# Artemis_HS_Expansion_Connector.net
KiCad netlist of a schematic drawn in Altium Designer
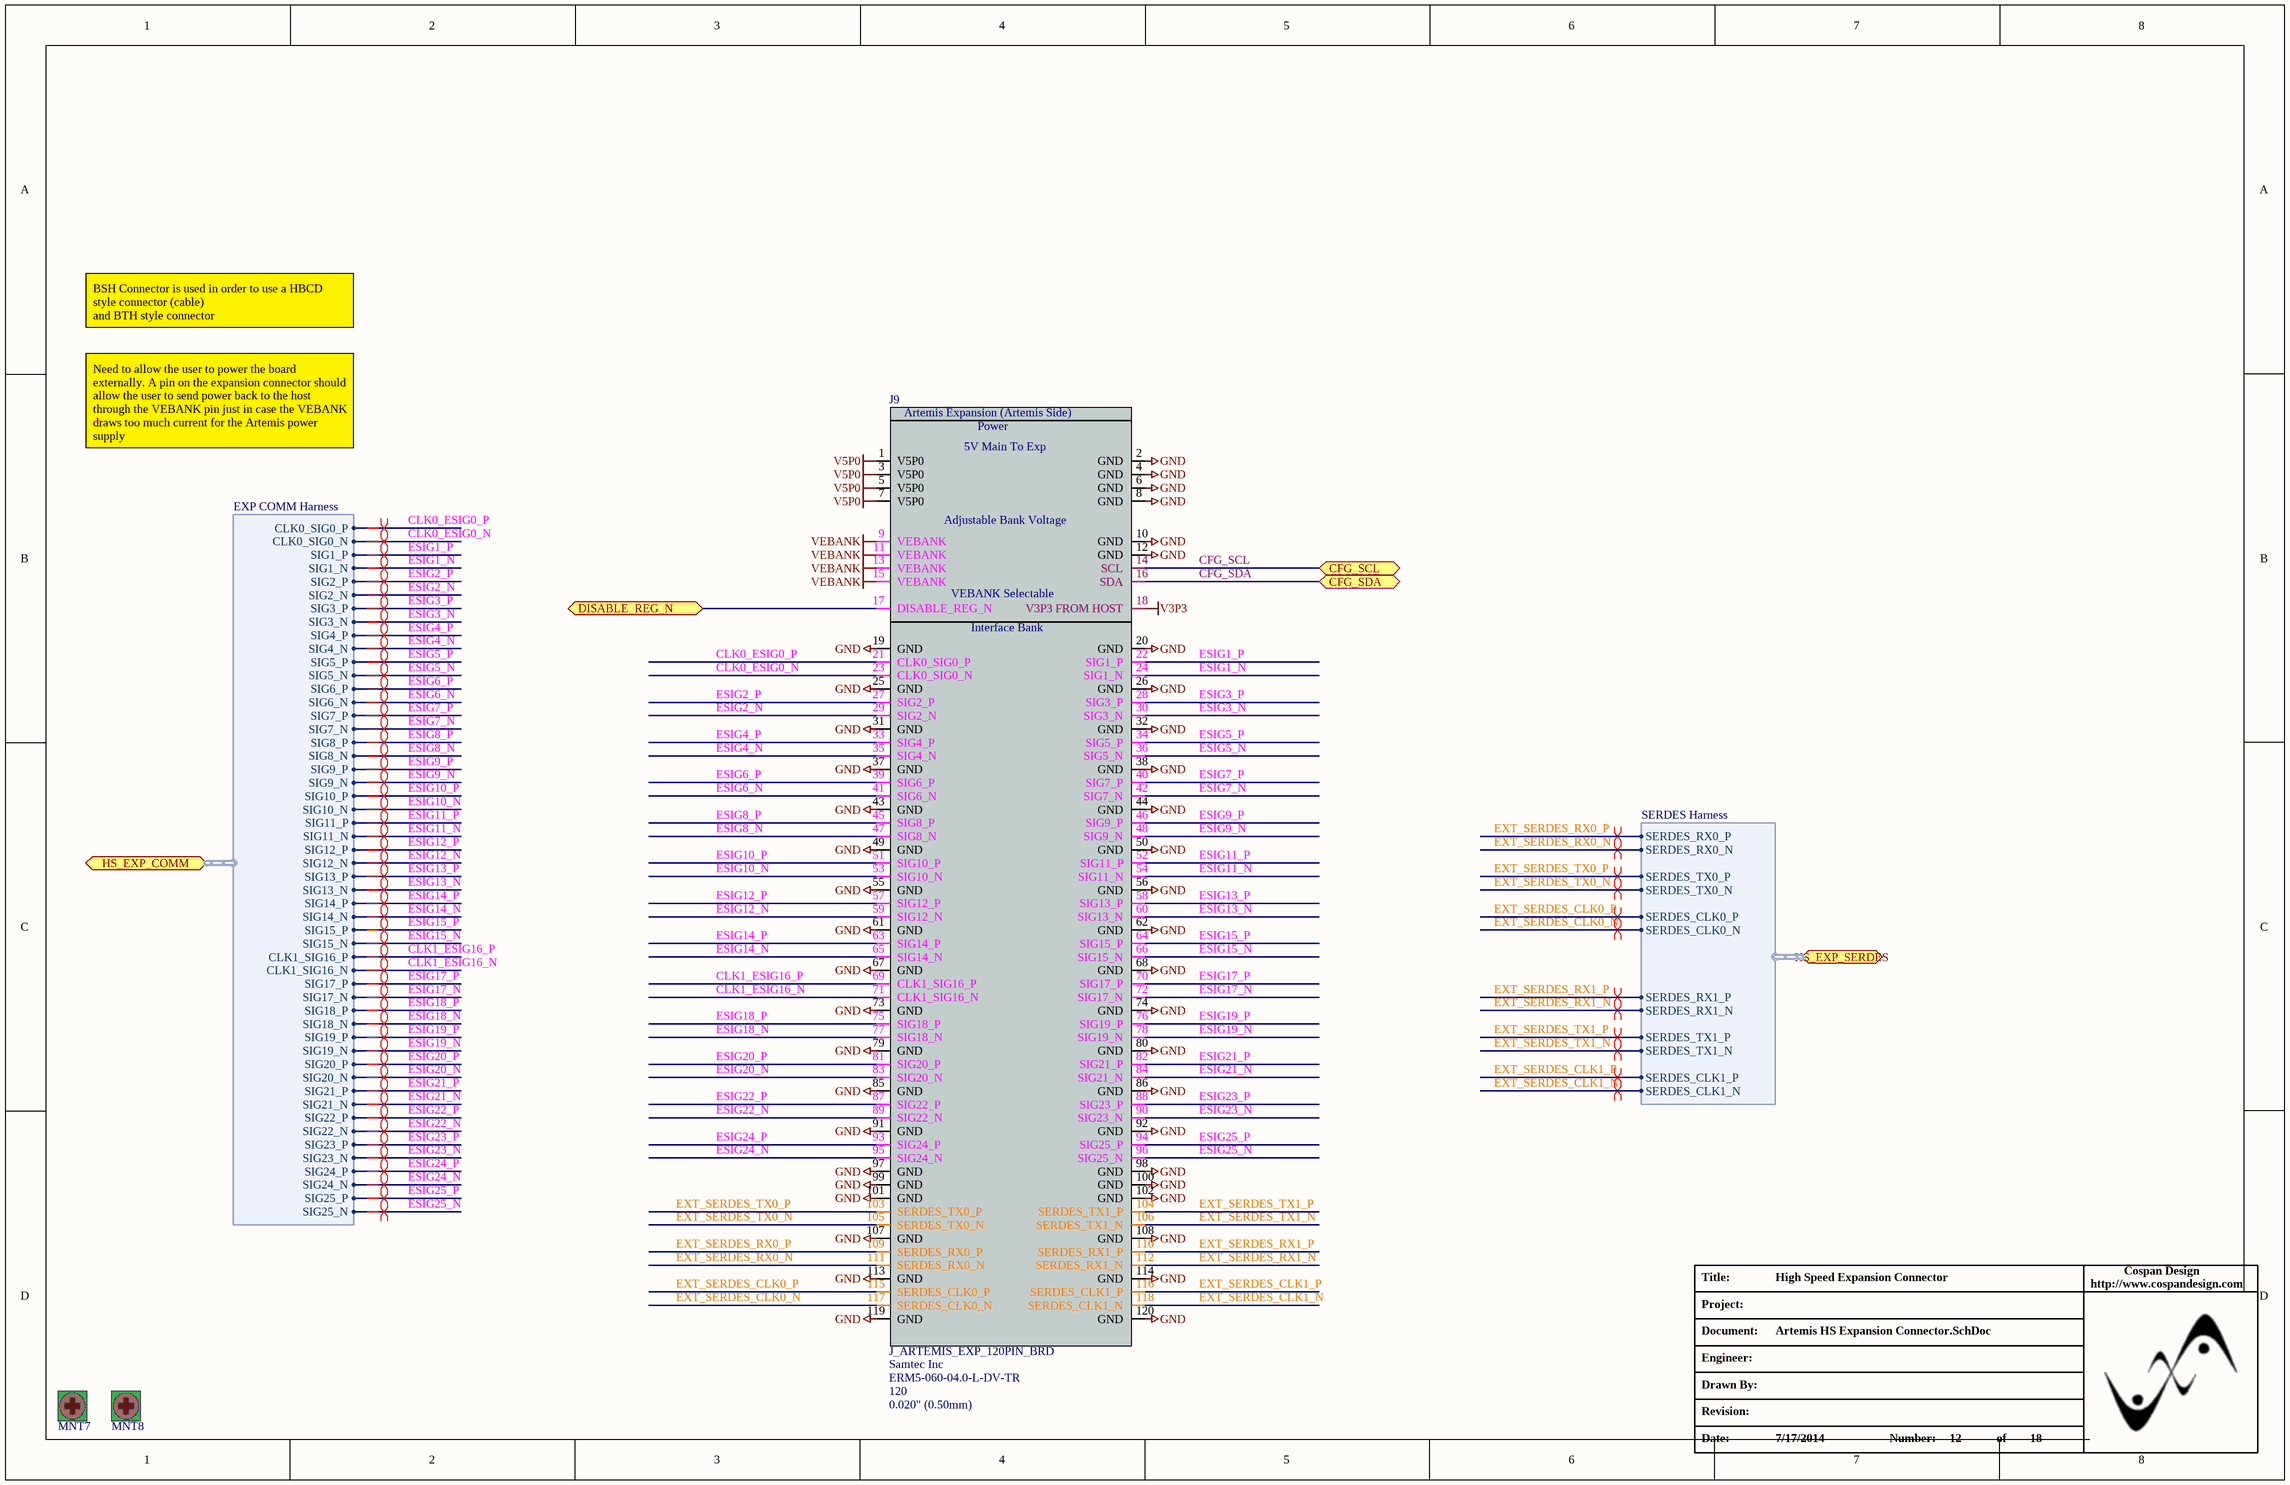
[diagram p0: Artemis HS Expansion Connector.SchDoc]

(export (version "E")
  (design (tool "Eeschema 10.0.6"))
  (components
    (comp (ref "J9")
      (value "J_ARTEMIS_EXP_120PIN_BRD")
      (footprint "ERM5-060-04.0-L-DV-TR")
      (description "CONN HDR 120POS 0.5MM SMD")
      (fields
        (field (name "MANUFACTURER") "Samtec Inc")
        (field (name "MANUFACTURER PART NUMBER") "ERM5-060-04.0-L-DV-TR")
        (field (name "NUMBER OF POSITIONS") "120")
        (field (name "PITCH") "0.020\" (0.50mm)")
      )
      (libsource (lib "Main LibraryX") (part "J_ARTEMIS_EXP_120PIN_BRD"))
    )
    (comp (ref "MNT7")
      (value "Mounting Hole")
      (footprint "MNT_4-40")
      (libsource (lib "Main Library") (part "MNT_440_HOLE"))
    )
    (comp (ref "MNT8")
      (value "Mounting Hole")
      (footprint "MNT_4-40")
      (libsource (lib "Main Library") (part "MNT_440_HOLE"))
    )
  )
  (nets
    (net (code "5") (name "/CFG_SCL") (class "Default")
      (node (ref "J9") (pin "14") (pinfunction "SCL_14") (pintype "passive"))
    )
    (net (code "6") (name "/CFG_SDA") (class "Default")
      (node (ref "J9") (pin "16") (pinfunction "SDA_16") (pintype "passive"))
    )
    (net (code "7") (name "/CLK0_ESIG0_N") (class "Default")
      (node (ref "J9") (pin "23") (pinfunction "CLK0_SIG0_N_23") (pintype "passive"))
    )
    (net (code "8") (name "/CLK0_ESIG0_P") (class "Default")
      (node (ref "J9") (pin "21") (pinfunction "CLK0_SIG0_P_21") (pintype "passive"))
    )
    (net (code "9") (name "/CLK1_ESIG16_N") (class "Default")
      (node (ref "J9") (pin "71") (pinfunction "CLK1_SIG16_N_71") (pintype "passive"))
    )
    (net (code "10") (name "/CLK1_ESIG16_P") (class "Default")
      (node (ref "J9") (pin "69") (pinfunction "CLK1_SIG16_P_69") (pintype "passive"))
    )
    (net (code "11") (name "/DISABLE_REG_N") (class "Default")
      (node (ref "J9") (pin "17") (pinfunction "DISABLE_REG_N_17") (pintype "passive"))
    )
    (net (code "12") (name "/ESIG1_N") (class "Default")
      (node (ref "J9") (pin "24") (pinfunction "SIG1_N_24") (pintype "passive"))
    )
    (net (code "13") (name "/ESIG1_P") (class "Default")
      (node (ref "J9") (pin "22") (pinfunction "SIG1_P_22") (pintype "passive"))
    )
    (net (code "14") (name "/ESIG2_N") (class "Default")
      (node (ref "J9") (pin "29") (pinfunction "SIG2_N_29") (pintype "passive"))
    )
    (net (code "15") (name "/ESIG2_P") (class "Default")
      (node (ref "J9") (pin "27") (pinfunction "SIG2_P_27") (pintype "passive"))
    )
    (net (code "16") (name "/ESIG3_N") (class "Default")
      (node (ref "J9") (pin "30") (pinfunction "SIG3_N_30") (pintype "passive"))
    )
    (net (code "17") (name "/ESIG3_P") (class "Default")
      (node (ref "J9") (pin "28") (pinfunction "SIG3_P_28") (pintype "passive"))
    )
    (net (code "18") (name "/ESIG4_N") (class "Default")
      (node (ref "J9") (pin "35") (pinfunction "SIG4_N_35") (pintype "passive"))
    )
    (net (code "19") (name "/ESIG4_P") (class "Default")
      (node (ref "J9") (pin "33") (pinfunction "SIG4_P_33") (pintype "passive"))
    )
    (net (code "20") (name "/ESIG5_N") (class "Default")
      (node (ref "J9") (pin "36") (pinfunction "SIG5_N_36") (pintype "passive"))
    )
    (net (code "21") (name "/ESIG5_P") (class "Default")
      (node (ref "J9") (pin "34") (pinfunction "SIG5_P_34") (pintype "passive"))
    )
    (net (code "22") (name "/ESIG6_N") (class "Default")
      (node (ref "J9") (pin "41") (pinfunction "SIG6_N_41") (pintype "passive"))
    )
    (net (code "23") (name "/ESIG6_P") (class "Default")
      (node (ref "J9") (pin "39") (pinfunction "SIG6_P_39") (pintype "passive"))
    )
    (net (code "24") (name "/ESIG7_N") (class "Default")
      (node (ref "J9") (pin "42") (pinfunction "SIG7_N_42") (pintype "passive"))
    )
    (net (code "25") (name "/ESIG7_P") (class "Default")
      (node (ref "J9") (pin "40") (pinfunction "SIG7_P_40") (pintype "passive"))
    )
    (net (code "26") (name "/ESIG8_N") (class "Default")
      (node (ref "J9") (pin "47") (pinfunction "SIG8_N_47") (pintype "passive"))
    )
    (net (code "27") (name "/ESIG8_P") (class "Default")
      (node (ref "J9") (pin "45") (pinfunction "SIG8_P_45") (pintype "passive"))
    )
    (net (code "28") (name "/ESIG9_N") (class "Default")
      (node (ref "J9") (pin "48") (pinfunction "SIG9_N_48") (pintype "passive"))
    )
    (net (code "29") (name "/ESIG9_P") (class "Default")
      (node (ref "J9") (pin "46") (pinfunction "SIG9_P_46") (pintype "passive"))
    )
    (net (code "30") (name "/ESIG10_N") (class "Default")
      (node (ref "J9") (pin "53") (pinfunction "SIG10_N_53") (pintype "passive"))
    )
    (net (code "31") (name "/ESIG10_P") (class "Default")
      (node (ref "J9") (pin "51") (pinfunction "SIG10_P_51") (pintype "passive"))
    )
    (net (code "32") (name "/ESIG11_N") (class "Default")
      (node (ref "J9") (pin "54") (pinfunction "SIG11_N_54") (pintype "passive"))
    )
    (net (code "33") (name "/ESIG11_P") (class "Default")
      (node (ref "J9") (pin "52") (pinfunction "SIG11_P_52") (pintype "passive"))
    )
    (net (code "34") (name "/ESIG12_N") (class "Default")
      (node (ref "J9") (pin "59") (pinfunction "SIG12_N_59") (pintype "passive"))
    )
    (net (code "35") (name "/ESIG12_P") (class "Default")
      (node (ref "J9") (pin "57") (pinfunction "SIG12_P_57") (pintype "passive"))
    )
    (net (code "36") (name "/ESIG13_N") (class "Default")
      (node (ref "J9") (pin "60") (pinfunction "SIG13_N_60") (pintype "passive"))
    )
    (net (code "37") (name "/ESIG13_P") (class "Default")
      (node (ref "J9") (pin "58") (pinfunction "SIG13_P_58") (pintype "passive"))
    )
    (net (code "38") (name "/ESIG14_N") (class "Default")
      (node (ref "J9") (pin "65") (pinfunction "SIG14_N_65") (pintype "passive"))
    )
    (net (code "39") (name "/ESIG14_P") (class "Default")
      (node (ref "J9") (pin "63") (pinfunction "SIG14_P_63") (pintype "passive"))
    )
    (net (code "40") (name "/ESIG15_N") (class "Default")
      (node (ref "J9") (pin "66") (pinfunction "SIG15_N_66") (pintype "passive"))
    )
    (net (code "41") (name "/ESIG15_P") (class "Default")
      (node (ref "J9") (pin "64") (pinfunction "SIG15_P_64") (pintype "passive"))
    )
    (net (code "42") (name "/ESIG17_N") (class "Default")
      (node (ref "J9") (pin "72") (pinfunction "SIG17_N_72") (pintype "passive"))
    )
    (net (code "43") (name "/ESIG17_P") (class "Default")
      (node (ref "J9") (pin "70") (pinfunction "SIG17_P_70") (pintype "passive"))
    )
    (net (code "44") (name "/ESIG18_N") (class "Default")
      (node (ref "J9") (pin "77") (pinfunction "SIG18_N_77") (pintype "passive"))
    )
    (net (code "45") (name "/ESIG18_P") (class "Default")
      (node (ref "J9") (pin "75") (pinfunction "SIG18_P_75") (pintype "passive"))
    )
    (net (code "46") (name "/ESIG19_N") (class "Default")
      (node (ref "J9") (pin "78") (pinfunction "SIG19_N_78") (pintype "passive"))
    )
    (net (code "47") (name "/ESIG19_P") (class "Default")
      (node (ref "J9") (pin "76") (pinfunction "SIG19_P_76") (pintype "passive"))
    )
    (net (code "48") (name "/ESIG20_N") (class "Default")
      (node (ref "J9") (pin "83") (pinfunction "SIG20_N_83") (pintype "passive"))
    )
    (net (code "49") (name "/ESIG20_P") (class "Default")
      (node (ref "J9") (pin "81") (pinfunction "SIG20_P_81") (pintype "passive"))
    )
    (net (code "50") (name "/ESIG21_N") (class "Default")
      (node (ref "J9") (pin "84") (pinfunction "SIG21_N_84") (pintype "passive"))
    )
    (net (code "51") (name "/ESIG21_P") (class "Default")
      (node (ref "J9") (pin "82") (pinfunction "SIG21_P_82") (pintype "passive"))
    )
    (net (code "52") (name "/ESIG22_N") (class "Default")
      (node (ref "J9") (pin "89") (pinfunction "SIG22_N_89") (pintype "passive"))
    )
    (net (code "53") (name "/ESIG22_P") (class "Default")
      (node (ref "J9") (pin "87") (pinfunction "SIG22_P_87") (pintype "passive"))
    )
    (net (code "54") (name "/ESIG23_N") (class "Default")
      (node (ref "J9") (pin "90") (pinfunction "SIG23_N_90") (pintype "passive"))
    )
    (net (code "55") (name "/ESIG23_P") (class "Default")
      (node (ref "J9") (pin "88") (pinfunction "SIG23_P_88") (pintype "passive"))
    )
    (net (code "56") (name "/ESIG24_N") (class "Default")
      (node (ref "J9") (pin "95") (pinfunction "SIG24_N_95") (pintype "passive"))
    )
    (net (code "57") (name "/ESIG24_P") (class "Default")
      (node (ref "J9") (pin "93") (pinfunction "SIG24_P_93") (pintype "passive"))
    )
    (net (code "58") (name "/ESIG25_N") (class "Default")
      (node (ref "J9") (pin "96") (pinfunction "SIG25_N_96") (pintype "passive"))
    )
    (net (code "59") (name "/ESIG25_P") (class "Default")
      (node (ref "J9") (pin "94") (pinfunction "SIG25_P_94") (pintype "passive"))
    )
    (net (code "60") (name "/EXT_SERDES_CLK0_N") (class "Default")
      (node (ref "J9") (pin "117") (pinfunction "SERDES_CLK0_N_117") (pintype "passive"))
    )
    (net (code "61") (name "/EXT_SERDES_CLK0_P") (class "Default")
      (node (ref "J9") (pin "115") (pinfunction "SERDES_CLK0_P_115") (pintype "passive"))
    )
    (net (code "62") (name "/EXT_SERDES_CLK1_N") (class "Default")
      (node (ref "J9") (pin "118") (pinfunction "SERDES_CLK1_N_118") (pintype "passive"))
    )
    (net (code "63") (name "/EXT_SERDES_CLK1_P") (class "Default")
      (node (ref "J9") (pin "116") (pinfunction "SERDES_CLK1_P_116") (pintype "passive"))
    )
    (net (code "64") (name "/EXT_SERDES_RX0_N") (class "Default")
      (node (ref "J9") (pin "111") (pinfunction "SERDES_RX0_N_111") (pintype "passive"))
    )
    (net (code "65") (name "/EXT_SERDES_RX0_P") (class "Default")
      (node (ref "J9") (pin "109") (pinfunction "SERDES_RX0_P_109") (pintype "passive"))
    )
    (net (code "66") (name "/EXT_SERDES_RX1_N") (class "Default")
      (node (ref "J9") (pin "112") (pinfunction "SERDES_RX1_N_112") (pintype "passive"))
    )
    (net (code "67") (name "/EXT_SERDES_RX1_P") (class "Default")
      (node (ref "J9") (pin "110") (pinfunction "SERDES_RX1_P_110") (pintype "passive"))
    )
    (net (code "68") (name "/EXT_SERDES_TX0_N") (class "Default")
      (node (ref "J9") (pin "105") (pinfunction "SERDES_TX0_N_105") (pintype "passive"))
    )
    (net (code "69") (name "/EXT_SERDES_TX0_P") (class "Default")
      (node (ref "J9") (pin "103") (pinfunction "SERDES_TX0_P_103") (pintype "passive"))
    )
    (net (code "70") (name "/EXT_SERDES_TX1_N") (class "Default")
      (node (ref "J9") (pin "106") (pinfunction "SERDES_TX1_N_106") (pintype "passive"))
    )
    (net (code "71") (name "/EXT_SERDES_TX1_P") (class "Default")
      (node (ref "J9") (pin "104") (pinfunction "SERDES_TX1_P_104") (pintype "passive"))
    )
    (net (code "74") (name "GND") (class "Default")
      (node (ref "J9") (pin "10") (pinfunction "GND_10") (pintype "passive"))
      (node (ref "J9") (pin "100") (pinfunction "GND_100") (pintype "passive"))
      (node (ref "J9") (pin "101") (pinfunction "GND_101") (pintype "passive"))
      (node (ref "J9") (pin "102") (pinfunction "GND_102") (pintype "passive"))
      (node (ref "J9") (pin "107") (pinfunction "GND_107") (pintype "passive"))
      (node (ref "J9") (pin "108") (pinfunction "GND_108") (pintype "passive"))
      (node (ref "J9") (pin "113") (pinfunction "GND_113") (pintype "passive"))
      (node (ref "J9") (pin "114") (pinfunction "GND_114") (pintype "passive"))
      (node (ref "J9") (pin "119") (pinfunction "GND_119") (pintype "passive"))
      (node (ref "J9") (pin "12") (pinfunction "GND_12") (pintype "passive"))
      (node (ref "J9") (pin "120") (pinfunction "GND_120") (pintype "passive"))
      (node (ref "J9") (pin "19") (pinfunction "GND_19") (pintype "passive"))
      (node (ref "J9") (pin "2") (pinfunction "GND_2") (pintype "passive"))
      (node (ref "J9") (pin "20") (pinfunction "GND_20") (pintype "passive"))
      (node (ref "J9") (pin "25") (pinfunction "GND_25") (pintype "passive"))
      (node (ref "J9") (pin "26") (pinfunction "GND_26") (pintype "passive"))
      (node (ref "J9") (pin "31") (pinfunction "GND_31") (pintype "passive"))
      (node (ref "J9") (pin "32") (pinfunction "GND_32") (pintype "passive"))
      (node (ref "J9") (pin "37") (pinfunction "GND_37") (pintype "passive"))
      (node (ref "J9") (pin "38") (pinfunction "GND_38") (pintype "passive"))
      (node (ref "J9") (pin "4") (pinfunction "GND_4") (pintype "passive"))
      (node (ref "J9") (pin "43") (pinfunction "GND_43") (pintype "passive"))
      (node (ref "J9") (pin "44") (pinfunction "GND_44") (pintype "passive"))
      (node (ref "J9") (pin "49") (pinfunction "GND_49") (pintype "passive"))
      (node (ref "J9") (pin "50") (pinfunction "GND_50") (pintype "passive"))
      (node (ref "J9") (pin "55") (pinfunction "GND_55") (pintype "passive"))
      (node (ref "J9") (pin "56") (pinfunction "GND_56") (pintype "passive"))
      (node (ref "J9") (pin "6") (pinfunction "GND_6") (pintype "passive"))
      (node (ref "J9") (pin "61") (pinfunction "GND_61") (pintype "passive"))
      (node (ref "J9") (pin "62") (pinfunction "GND_62") (pintype "passive"))
      (node (ref "J9") (pin "67") (pinfunction "GND_67") (pintype "passive"))
      (node (ref "J9") (pin "68") (pinfunction "GND_68") (pintype "passive"))
      (node (ref "J9") (pin "73") (pinfunction "GND_73") (pintype "passive"))
      (node (ref "J9") (pin "74") (pinfunction "GND_74") (pintype "passive"))
      (node (ref "J9") (pin "79") (pinfunction "GND_79") (pintype "passive"))
      (node (ref "J9") (pin "8") (pinfunction "GND_8") (pintype "passive"))
      (node (ref "J9") (pin "80") (pinfunction "GND_80") (pintype "passive"))
      (node (ref "J9") (pin "85") (pinfunction "GND_85") (pintype "passive"))
      (node (ref "J9") (pin "86") (pinfunction "GND_86") (pintype "passive"))
      (node (ref "J9") (pin "91") (pinfunction "GND_91") (pintype "passive"))
      (node (ref "J9") (pin "92") (pinfunction "GND_92") (pintype "passive"))
      (node (ref "J9") (pin "97") (pinfunction "GND_97") (pintype "passive"))
      (node (ref "J9") (pin "98") (pinfunction "GND_98") (pintype "passive"))
      (node (ref "J9") (pin "99") (pinfunction "GND_99") (pintype "passive"))
    )
    (net (code "75") (name "V3P3") (class "Default")
      (node (ref "J9") (pin "18") (pinfunction "V3P3_FROM_HOST_18") (pintype "passive"))
    )
    (net (code "76") (name "V5P0") (class "Default")
      (node (ref "J9") (pin "1") (pinfunction "V5P0_1") (pintype "passive"))
      (node (ref "J9") (pin "3") (pinfunction "V5P0_3") (pintype "passive"))
      (node (ref "J9") (pin "5") (pinfunction "V5P0_5") (pintype "passive"))
      (node (ref "J9") (pin "7") (pinfunction "V5P0_7") (pintype "passive"))
    )
    (net (code "77") (name "VEBANK") (class "Default")
      (node (ref "J9") (pin "11") (pinfunction "VEBANK_11") (pintype "passive"))
      (node (ref "J9") (pin "13") (pinfunction "VEBANK_13") (pintype "passive"))
      (node (ref "J9") (pin "15") (pinfunction "VEBANK_15") (pintype "passive"))
      (node (ref "J9") (pin "9") (pinfunction "VEBANK_9") (pintype "passive"))
    )
  )
)
